# STM32.net
KiCad netlist of a schematic drawn in Altium Designer
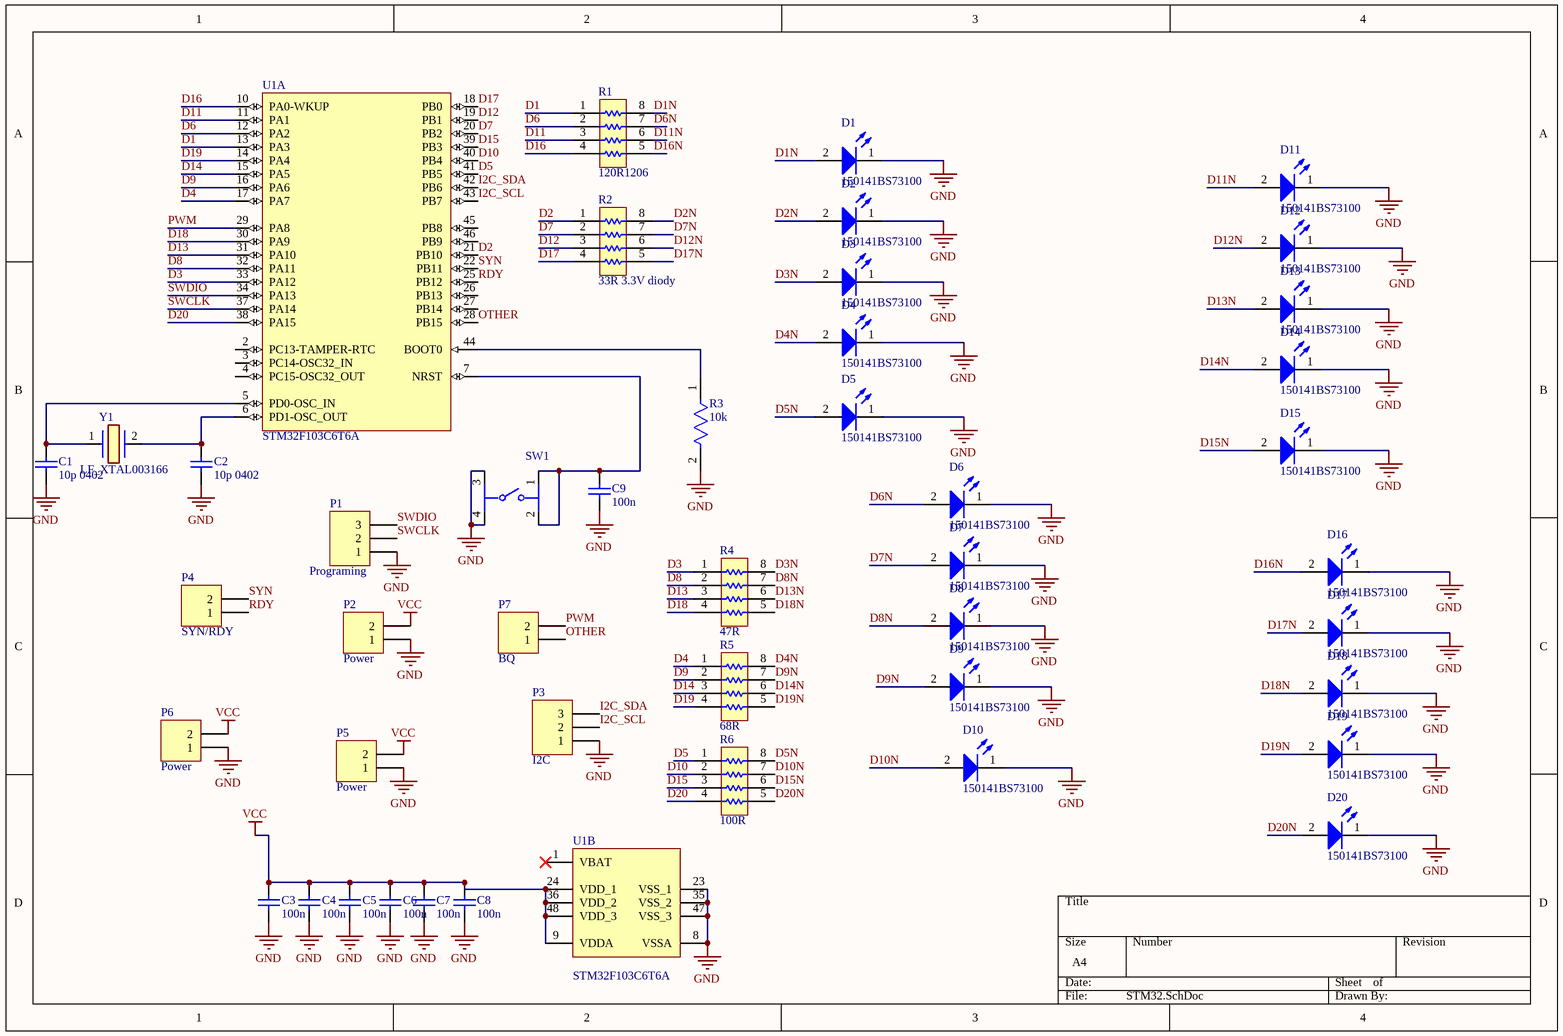
[diagram p0: STM32.SchDoc]

(export (version "E")
  (design (tool "Eeschema 10.0.6"))
  (components
    (comp (ref "C1")
      (value "10p 0402")
      (footprint "CAPC1006X50X20ML10T10")
      (fields
        (field (name "MANUFACTURER") "AVX Interconnect / Elco")
        (field (name "PART NUMBER") "0402YJ100FBSTR")
      )
      (libsource (lib "Altium Content Vault") (part "CAP"))
    )
    (comp (ref "C2")
      (value "10p 0402")
      (footprint "CAPC1006X50X20ML10T10")
      (fields
        (field (name "MANUFACTURER") "AVX Interconnect / Elco")
        (field (name "PART NUMBER") "0402YJ100FBSTR")
      )
      (libsource (lib "Altium Content Vault") (part "CAP"))
    )
    (comp (ref "C3")
      (value "100n")
      (footprint "1608[0603]")
      (description "Capacitor (Semiconductor SIM Model)")
      (fields (field (name "PUBLISHER") "Altium Limited"))
      (libsource (lib "Miscellaneous Devices") (part "Cap Semi"))
    )
    (comp (ref "C4")
      (value "100n")
      (footprint "1608[0603]")
      (description "Capacitor (Semiconductor SIM Model)")
      (fields (field (name "PUBLISHER") "Altium Limited"))
      (libsource (lib "Miscellaneous Devices") (part "Cap Semi"))
    )
    (comp (ref "C5")
      (value "100n")
      (footprint "1608[0603]")
      (description "Capacitor (Semiconductor SIM Model)")
      (fields (field (name "PUBLISHER") "Altium Limited"))
      (libsource (lib "Miscellaneous Devices") (part "Cap Semi"))
    )
    (comp (ref "C6")
      (value "100n")
      (footprint "1608[0603]")
      (description "Capacitor (Semiconductor SIM Model)")
      (fields (field (name "PUBLISHER") "Altium Limited"))
      (libsource (lib "Miscellaneous Devices") (part "Cap Semi"))
    )
    (comp (ref "C7")
      (value "100n")
      (footprint "1608[0603]")
      (description "Capacitor (Semiconductor SIM Model)")
      (fields (field (name "PUBLISHER") "Altium Limited"))
      (libsource (lib "Miscellaneous Devices") (part "Cap Semi"))
    )
    (comp (ref "C8")
      (value "100n")
      (footprint "1608[0603]")
      (description "Capacitor (Semiconductor SIM Model)")
      (fields (field (name "PUBLISHER") "Altium Limited"))
      (libsource (lib "Miscellaneous Devices") (part "Cap Semi"))
    )
    (comp (ref "C9")
      (value "100n")
      (footprint "1608[0603]")
      (description "Capacitor (Semiconductor SIM Model)")
      (fields (field (name "PUBLISHER") "Altium Limited"))
      (libsource (lib "Miscellaneous Devices") (part "Cap Semi"))
    )
    (comp (ref "D1")
      (value "150141BS73100")
      (footprint "WL-SMTW_3528")
      (libsource (lib "Altium Content Vault") (part "LED_Blue_2A-1K"))
    )
    (comp (ref "D2")
      (value "150141BS73100")
      (footprint "WL-SMTW_3528")
      (libsource (lib "Altium Content Vault") (part "LED_Blue_2A-1K"))
    )
    (comp (ref "D3")
      (value "150141BS73100")
      (footprint "WL-SMTW_3528")
      (libsource (lib "Altium Content Vault") (part "LED_Blue_2A-1K"))
    )
    (comp (ref "D4")
      (value "150141BS73100")
      (footprint "WL-SMTW_3528")
      (libsource (lib "Altium Content Vault") (part "LED_Blue_2A-1K"))
    )
    (comp (ref "D5")
      (value "150141BS73100")
      (footprint "WL-SMTW_3528")
      (libsource (lib "Altium Content Vault") (part "LED_Blue_2A-1K"))
    )
    (comp (ref "D6")
      (value "150141BS73100")
      (footprint "WL-SMTW_3528")
      (libsource (lib "Altium Content Vault") (part "LED_Blue_2A-1K"))
    )
    (comp (ref "D7")
      (value "150141BS73100")
      (footprint "WL-SMTW_3528")
      (libsource (lib "Altium Content Vault") (part "LED_Blue_2A-1K"))
    )
    (comp (ref "D8")
      (value "150141BS73100")
      (footprint "WL-SMTW_3528")
      (libsource (lib "Altium Content Vault") (part "LED_Blue_2A-1K"))
    )
    (comp (ref "D9")
      (value "150141BS73100")
      (footprint "WL-SMTW_3528")
      (libsource (lib "Altium Content Vault") (part "LED_Blue_2A-1K"))
    )
    (comp (ref "D10")
      (value "150141BS73100")
      (footprint "WL-SMTW_3528")
      (libsource (lib "Altium Content Vault") (part "LED_Blue_2A-1K"))
    )
    (comp (ref "D11")
      (value "150141BS73100")
      (footprint "WL-SMTW_3528")
      (libsource (lib "Altium Content Vault") (part "LED_Blue_2A-1K"))
    )
    (comp (ref "D12")
      (value "150141BS73100")
      (footprint "WL-SMTW_3528")
      (libsource (lib "Altium Content Vault") (part "LED_Blue_2A-1K"))
    )
    (comp (ref "D13")
      (value "150141BS73100")
      (footprint "WL-SMTW_3528")
      (libsource (lib "Altium Content Vault") (part "LED_Blue_2A-1K"))
    )
    (comp (ref "D14")
      (value "150141BS73100")
      (footprint "WL-SMTW_3528")
      (libsource (lib "Altium Content Vault") (part "LED_Blue_2A-1K"))
    )
    (comp (ref "D15")
      (value "150141BS73100")
      (footprint "WL-SMTW_3528")
      (libsource (lib "Altium Content Vault") (part "LED_Blue_2A-1K"))
    )
    (comp (ref "D16")
      (value "150141BS73100")
      (footprint "WL-SMTW_3528")
      (libsource (lib "Altium Content Vault") (part "LED_Blue_2A-1K"))
    )
    (comp (ref "D17")
      (value "150141BS73100")
      (footprint "WL-SMTW_3528")
      (libsource (lib "Altium Content Vault") (part "LED_Blue_2A-1K"))
    )
    (comp (ref "D18")
      (value "150141BS73100")
      (footprint "WL-SMTW_3528")
      (libsource (lib "Altium Content Vault") (part "LED_Blue_2A-1K"))
    )
    (comp (ref "D19")
      (value "150141BS73100")
      (footprint "WL-SMTW_3528")
      (libsource (lib "Altium Content Vault") (part "LED_Blue_2A-1K"))
    )
    (comp (ref "D20")
      (value "150141BS73100")
      (footprint "WL-SMTW_3528")
      (libsource (lib "Altium Content Vault") (part "LED_Blue_2A-1K"))
    )
    (comp (ref "P1")
      (value "Programing")
      (footprint "HDR1X3")
      (description "Header, 3-Pin")
      (fields (field (name "PUBLISHER") "Altium Limited"))
      (libsource (lib "PreEngProject") (part "Header 3"))
    )
    (comp (ref "P2")
      (value "Power")
      (footprint "HDR1X2")
      (description "Header, 2-Pin")
      (fields (field (name "PUBLISHER") "Altium Limited"))
      (libsource (lib "Miscellaneous Connectors") (part "Header 2"))
    )
    (comp (ref "P3")
      (value "I2C")
      (footprint "HDR1X3")
      (description "Header, 3-Pin")
      (fields (field (name "PUBLISHER") "Altium Limited"))
      (libsource (lib "PreEngProject") (part "Header 3"))
    )
    (comp (ref "P4")
      (value "SYN/RDY")
      (footprint "HDR1X2")
      (description "Header, 2-Pin")
      (fields (field (name "PUBLISHER") "Altium Limited"))
      (libsource (lib "Miscellaneous Connectors") (part "Header 2"))
    )
    (comp (ref "P5")
      (value "Power")
      (footprint "HDR1X2")
      (description "Header, 2-Pin")
      (fields (field (name "PUBLISHER") "Altium Limited"))
      (libsource (lib "Miscellaneous Connectors") (part "Header 2"))
    )
    (comp (ref "P6")
      (value "Power")
      (footprint "HDR1X2")
      (description "Header, 2-Pin")
      (fields (field (name "PUBLISHER") "Altium Limited"))
      (libsource (lib "Miscellaneous Connectors") (part "Header 2"))
    )
    (comp (ref "P7")
      (value "BQ")
      (footprint "HDR1X2")
      (description "Header, 2-Pin")
      (fields (field (name "PUBLISHER") "Altium Limited"))
      (libsource (lib "Miscellaneous Connectors") (part "Header 2"))
    )
    (comp (ref "R1")
      (value "120R1206")
      (footprint "BOUR-CAY16-J4_V")
      (description "Chip Resistor Array, 1 KOhm, +/- 5%, 62.5 mW, -55 to 125 degC, 8-Pin SMD, RoHS, Tape and Reel")
      (fields (field (name "TOLERANCE") "1%"))
      (libsource (lib "Altium Content Vault") (part "RES-P-8"))
    )
    (comp (ref "R2")
      (value "33R 3.3V diody")
      (footprint "BOUR-CAY16-J4_V")
      (description "Chip Resistor Array, 1 KOhm, +/- 5%, 62.5 mW, -55 to 125 degC, 8-Pin SMD, RoHS, Tape and Reel")
      (fields (field (name "TOLERANCE") "1%"))
      (libsource (lib "Altium Content Vault") (part "RES-P-8"))
    )
    (comp (ref "R3")
      (value "10k")
      (footprint "FP-CRCW0603-e3-MFG")
      (description "RES Thick Film, 10kΩ, 1%, 0.1W, 100ppm/°C, 0603")
      (fields (field (name "TOLERANCE") "1%"))
      (libsource (lib "Altium Content Vault") (part "1029c3af85768c4190bb7ad29bc67b5"))
    )
    (comp (ref "R4")
      (value "47R")
      (footprint "BOUR-CAY16-J4_V")
      (description "Chip Resistor Array, 1 KOhm, +/- 5%, 62.5 mW, -55 to 125 degC, 8-Pin SMD, RoHS, Tape and Reel")
      (fields (field (name "TOLERANCE") "1%"))
      (libsource (lib "Altium Content Vault") (part "RES-P-8"))
    )
    (comp (ref "R5")
      (value "68R")
      (footprint "BOUR-CAY16-J4_V")
      (description "Chip Resistor Array, 1 KOhm, +/- 5%, 62.5 mW, -55 to 125 degC, 8-Pin SMD, RoHS, Tape and Reel")
      (fields (field (name "TOLERANCE") "1%"))
      (libsource (lib "Altium Content Vault") (part "RES-P-8"))
    )
    (comp (ref "R6")
      (value "100R")
      (footprint "BOUR-CAY16-J4_V")
      (description "Chip Resistor Array, 1 KOhm, +/- 5%, 62.5 mW, -55 to 125 degC, 8-Pin SMD, RoHS, Tape and Reel")
      (fields (field (name "TOLERANCE") "1%"))
      (libsource (lib "Altium Content Vault") (part "RES-P-8"))
    )
    (comp (ref "SW1")
      (value "PTS645SM43SMTR92LFS")
      (footprint "FP-PTS645SM43SMTR92LFS-MFG")
      (description "SWITCH TACTILE SPST-NO 0.05A 12V")
      (libsource (lib "Altium Content Vault") (part "1adf0dd01260c80cf25a44bfd6b99ba"))
    )
    (comp (ref "U1")
      (value "STM32F103C6T6A")
      (footprint "STM-LQFP48_L")
      (libsource (lib "Altium Content Vault") (part "MC-ARM-STM32F103X4_6-SQ48"))
    )
    (comp (ref "Y1")
      (value "LF_XTAL003166")
      (footprint "SamacSys:LFXTAL003166")
      (description "Crystal or Oscillator")
      (fields (field (name "MANUFACTURER_PART_NUMBER") "LF XTAL003166"))
      (libsource (lib "*") (part "LF_XTAL003166"))
    )
  )
  (nets
    (net (code "1") (name "/D1") (class "Default")
      (node (ref "R1") (pin "1") (pinfunction "1_1") (pintype "passive"))
      (node (ref "U1") (pin "13") (pinfunction "PA3_13") (pintype "bidirectional"))
    )
    (net (code "2") (name "/D1N") (class "Default")
      (node (ref "D1") (pin "2") (pinfunction "A_2") (pintype "passive"))
      (node (ref "R1") (pin "8") (pinfunction "8_8") (pintype "passive"))
    )
    (net (code "3") (name "/D2") (class "Default")
      (node (ref "R2") (pin "1") (pinfunction "1_1") (pintype "passive"))
      (node (ref "U1") (pin "21") (pinfunction "PB10_21") (pintype "bidirectional"))
    )
    (net (code "4") (name "/D2N") (class "Default")
      (node (ref "D2") (pin "2") (pinfunction "A_2") (pintype "passive"))
      (node (ref "R2") (pin "8") (pinfunction "8_8") (pintype "passive"))
    )
    (net (code "5") (name "/D3") (class "Default")
      (node (ref "R4") (pin "1") (pinfunction "1_1") (pintype "passive"))
      (node (ref "U1") (pin "33") (pinfunction "PA12_33") (pintype "bidirectional"))
    )
    (net (code "6") (name "/D3N") (class "Default")
      (node (ref "D3") (pin "2") (pinfunction "A_2") (pintype "passive"))
      (node (ref "R4") (pin "8") (pinfunction "8_8") (pintype "passive"))
    )
    (net (code "7") (name "/D4") (class "Default")
      (node (ref "R5") (pin "1") (pinfunction "1_1") (pintype "passive"))
      (node (ref "U1") (pin "17") (pinfunction "PA7_17") (pintype "bidirectional"))
    )
    (net (code "8") (name "/D4N") (class "Default")
      (node (ref "D4") (pin "2") (pinfunction "A_2") (pintype "passive"))
      (node (ref "R5") (pin "8") (pinfunction "8_8") (pintype "passive"))
    )
    (net (code "9") (name "/D5") (class "Default")
      (node (ref "R6") (pin "1") (pinfunction "1_1") (pintype "passive"))
      (node (ref "U1") (pin "41") (pinfunction "PB5_41") (pintype "bidirectional"))
    )
    (net (code "10") (name "/D5N") (class "Default")
      (node (ref "D5") (pin "2") (pinfunction "A_2") (pintype "passive"))
      (node (ref "R6") (pin "8") (pinfunction "8_8") (pintype "passive"))
    )
    (net (code "11") (name "/D6") (class "Default")
      (node (ref "R1") (pin "2") (pinfunction "2_2") (pintype "passive"))
      (node (ref "U1") (pin "12") (pinfunction "PA2_12") (pintype "bidirectional"))
    )
    (net (code "12") (name "/D6N") (class "Default")
      (node (ref "D6") (pin "2") (pinfunction "A_2") (pintype "passive"))
      (node (ref "R1") (pin "7") (pinfunction "7_7") (pintype "passive"))
    )
    (net (code "13") (name "/D7") (class "Default")
      (node (ref "R2") (pin "2") (pinfunction "2_2") (pintype "passive"))
      (node (ref "U1") (pin "20") (pinfunction "PB2_20") (pintype "bidirectional"))
    )
    (net (code "14") (name "/D7N") (class "Default")
      (node (ref "D7") (pin "2") (pinfunction "A_2") (pintype "passive"))
      (node (ref "R2") (pin "7") (pinfunction "7_7") (pintype "passive"))
    )
    (net (code "15") (name "/D8") (class "Default")
      (node (ref "R4") (pin "2") (pinfunction "2_2") (pintype "passive"))
      (node (ref "U1") (pin "32") (pinfunction "PA11_32") (pintype "bidirectional"))
    )
    (net (code "16") (name "/D8N") (class "Default")
      (node (ref "D8") (pin "2") (pinfunction "A_2") (pintype "passive"))
      (node (ref "R4") (pin "7") (pinfunction "7_7") (pintype "passive"))
    )
    (net (code "17") (name "/D9") (class "Default")
      (node (ref "R5") (pin "2") (pinfunction "2_2") (pintype "passive"))
      (node (ref "U1") (pin "16") (pinfunction "PA6_16") (pintype "bidirectional"))
    )
    (net (code "18") (name "/D9N") (class "Default")
      (node (ref "D9") (pin "2") (pinfunction "A_2") (pintype "passive"))
      (node (ref "R5") (pin "7") (pinfunction "7_7") (pintype "passive"))
    )
    (net (code "19") (name "/D10") (class "Default")
      (node (ref "R6") (pin "2") (pinfunction "2_2") (pintype "passive"))
      (node (ref "U1") (pin "40") (pinfunction "PB4_40") (pintype "bidirectional"))
    )
    (net (code "20") (name "/D10N") (class "Default")
      (node (ref "D10") (pin "2") (pinfunction "A_2") (pintype "passive"))
      (node (ref "R6") (pin "7") (pinfunction "7_7") (pintype "passive"))
    )
    (net (code "21") (name "/D11") (class "Default")
      (node (ref "R1") (pin "3") (pinfunction "3_3") (pintype "passive"))
      (node (ref "U1") (pin "11") (pinfunction "PA1_11") (pintype "bidirectional"))
    )
    (net (code "22") (name "/D11N") (class "Default")
      (node (ref "D11") (pin "2") (pinfunction "A_2") (pintype "passive"))
      (node (ref "R1") (pin "6") (pinfunction "6_6") (pintype "passive"))
    )
    (net (code "23") (name "/D12") (class "Default")
      (node (ref "R2") (pin "3") (pinfunction "3_3") (pintype "passive"))
      (node (ref "U1") (pin "19") (pinfunction "PB1_19") (pintype "bidirectional"))
    )
    (net (code "24") (name "/D12N") (class "Default")
      (node (ref "D12") (pin "2") (pinfunction "A_2") (pintype "passive"))
      (node (ref "R2") (pin "6") (pinfunction "6_6") (pintype "passive"))
    )
    (net (code "25") (name "/D13") (class "Default")
      (node (ref "R4") (pin "3") (pinfunction "3_3") (pintype "passive"))
      (node (ref "U1") (pin "31") (pinfunction "PA10_31") (pintype "bidirectional"))
    )
    (net (code "26") (name "/D13N") (class "Default")
      (node (ref "D13") (pin "2") (pinfunction "A_2") (pintype "passive"))
      (node (ref "R4") (pin "6") (pinfunction "6_6") (pintype "passive"))
    )
    (net (code "27") (name "/D14") (class "Default")
      (node (ref "R5") (pin "3") (pinfunction "3_3") (pintype "passive"))
      (node (ref "U1") (pin "15") (pinfunction "PA5_15") (pintype "bidirectional"))
    )
    (net (code "28") (name "/D14N") (class "Default")
      (node (ref "D14") (pin "2") (pinfunction "A_2") (pintype "passive"))
      (node (ref "R5") (pin "6") (pinfunction "6_6") (pintype "passive"))
    )
    (net (code "29") (name "/D15") (class "Default")
      (node (ref "R6") (pin "3") (pinfunction "3_3") (pintype "passive"))
      (node (ref "U1") (pin "39") (pinfunction "PB3_39") (pintype "bidirectional"))
    )
    (net (code "30") (name "/D15N") (class "Default")
      (node (ref "D15") (pin "2") (pinfunction "A_2") (pintype "passive"))
      (node (ref "R6") (pin "6") (pinfunction "6_6") (pintype "passive"))
    )
    (net (code "31") (name "/D16") (class "Default")
      (node (ref "R1") (pin "4") (pinfunction "4_4") (pintype "passive"))
      (node (ref "U1") (pin "10") (pinfunction "PA0-WKUP_10") (pintype "bidirectional"))
    )
    (net (code "32") (name "/D16N") (class "Default")
      (node (ref "D16") (pin "2") (pinfunction "A_2") (pintype "passive"))
      (node (ref "R1") (pin "5") (pinfunction "5_5") (pintype "passive"))
    )
    (net (code "33") (name "/D17") (class "Default")
      (node (ref "R2") (pin "4") (pinfunction "4_4") (pintype "passive"))
      (node (ref "U1") (pin "18") (pinfunction "PB0_18") (pintype "bidirectional"))
    )
    (net (code "34") (name "/D17N") (class "Default")
      (node (ref "D17") (pin "2") (pinfunction "A_2") (pintype "passive"))
      (node (ref "R2") (pin "5") (pinfunction "5_5") (pintype "passive"))
    )
    (net (code "35") (name "/D18") (class "Default")
      (node (ref "R4") (pin "4") (pinfunction "4_4") (pintype "passive"))
      (node (ref "U1") (pin "30") (pinfunction "PA9_30") (pintype "bidirectional"))
    )
    (net (code "36") (name "/D18N") (class "Default")
      (node (ref "D18") (pin "2") (pinfunction "A_2") (pintype "passive"))
      (node (ref "R4") (pin "5") (pinfunction "5_5") (pintype "passive"))
    )
    (net (code "37") (name "/D19") (class "Default")
      (node (ref "R5") (pin "4") (pinfunction "4_4") (pintype "passive"))
      (node (ref "U1") (pin "14") (pinfunction "PA4_14") (pintype "bidirectional"))
    )
    (net (code "38") (name "/D19N") (class "Default")
      (node (ref "D19") (pin "2") (pinfunction "A_2") (pintype "passive"))
      (node (ref "R5") (pin "5") (pinfunction "5_5") (pintype "passive"))
    )
    (net (code "39") (name "/D20") (class "Default")
      (node (ref "R6") (pin "4") (pinfunction "4_4") (pintype "passive"))
      (node (ref "U1") (pin "38") (pinfunction "PA15_38") (pintype "bidirectional"))
    )
    (net (code "40") (name "/D20N") (class "Default")
      (node (ref "D20") (pin "2") (pinfunction "A_2") (pintype "passive"))
      (node (ref "R6") (pin "5") (pinfunction "5_5") (pintype "passive"))
    )
    (net (code "41") (name "/I2C_SCL") (class "Default")
      (node (ref "P3") (pin "2") (pinfunction "2_2") (pintype "passive"))
      (node (ref "U1") (pin "43") (pinfunction "PB7_43") (pintype "bidirectional"))
    )
    (net (code "42") (name "/I2C_SDA") (class "Default")
      (node (ref "P3") (pin "3") (pinfunction "3_3") (pintype "passive"))
      (node (ref "U1") (pin "42") (pinfunction "PB6_42") (pintype "bidirectional"))
    )
    (net (code "43") (name "/OTHER") (class "Default")
      (node (ref "P7") (pin "1") (pinfunction "1_1") (pintype "passive"))
      (node (ref "U1") (pin "28") (pinfunction "PB15_28") (pintype "bidirectional"))
    )
    (net (code "44") (name "/PWM") (class "Default")
      (node (ref "P7") (pin "2") (pinfunction "2_2") (pintype "passive"))
      (node (ref "U1") (pin "29") (pinfunction "PA8_29") (pintype "bidirectional"))
    )
    (net (code "45") (name "/RDY") (class "Default")
      (node (ref "P4") (pin "1") (pinfunction "1_1") (pintype "passive"))
      (node (ref "U1") (pin "25") (pinfunction "PB12_25") (pintype "bidirectional"))
    )
    (net (code "46") (name "/SWCLK") (class "Default")
      (node (ref "P1") (pin "2") (pinfunction "2_2") (pintype "passive"))
      (node (ref "U1") (pin "37") (pinfunction "PA14_37") (pintype "bidirectional"))
    )
    (net (code "47") (name "/SWDIO") (class "Default")
      (node (ref "P1") (pin "3") (pinfunction "3_3") (pintype "passive"))
      (node (ref "U1") (pin "34") (pinfunction "PA13_34") (pintype "bidirectional"))
    )
    (net (code "48") (name "/SYN") (class "Default")
      (node (ref "P4") (pin "2") (pinfunction "2_2") (pintype "passive"))
      (node (ref "U1") (pin "22") (pinfunction "PB11_22") (pintype "bidirectional"))
    )
    (net (code "49") (name "GND") (class "Default")
      (node (ref "C1") (pin "1") (pinfunction "1_1") (pintype "passive"))
      (node (ref "C2") (pin "1") (pinfunction "1_1") (pintype "passive"))
      (node (ref "C3") (pin "1") (pinfunction "1_1") (pintype "passive"))
      (node (ref "C4") (pin "1") (pinfunction "1_1") (pintype "passive"))
      (node (ref "C5") (pin "1") (pinfunction "1_1") (pintype "passive"))
      (node (ref "C6") (pin "1") (pinfunction "1_1") (pintype "passive"))
      (node (ref "C7") (pin "1") (pinfunction "1_1") (pintype "passive"))
      (node (ref "C8") (pin "1") (pinfunction "1_1") (pintype "passive"))
      (node (ref "C9") (pin "1") (pinfunction "1_1") (pintype "passive"))
      (node (ref "D1") (pin "1") (pinfunction "K_1") (pintype "passive"))
      (node (ref "D10") (pin "1") (pinfunction "K_1") (pintype "passive"))
      (node (ref "D11") (pin "1") (pinfunction "K_1") (pintype "passive"))
      (node (ref "D12") (pin "1") (pinfunction "K_1") (pintype "passive"))
      (node (ref "D13") (pin "1") (pinfunction "K_1") (pintype "passive"))
      (node (ref "D14") (pin "1") (pinfunction "K_1") (pintype "passive"))
      (node (ref "D15") (pin "1") (pinfunction "K_1") (pintype "passive"))
      (node (ref "D16") (pin "1") (pinfunction "K_1") (pintype "passive"))
      (node (ref "D17") (pin "1") (pinfunction "K_1") (pintype "passive"))
      (node (ref "D18") (pin "1") (pinfunction "K_1") (pintype "passive"))
      (node (ref "D19") (pin "1") (pinfunction "K_1") (pintype "passive"))
      (node (ref "D2") (pin "1") (pinfunction "K_1") (pintype "passive"))
      (node (ref "D20") (pin "1") (pinfunction "K_1") (pintype "passive"))
      (node (ref "D3") (pin "1") (pinfunction "K_1") (pintype "passive"))
      (node (ref "D4") (pin "1") (pinfunction "K_1") (pintype "passive"))
      (node (ref "D5") (pin "1") (pinfunction "K_1") (pintype "passive"))
      (node (ref "D6") (pin "1") (pinfunction "K_1") (pintype "passive"))
      (node (ref "D7") (pin "1") (pinfunction "K_1") (pintype "passive"))
      (node (ref "D8") (pin "1") (pinfunction "K_1") (pintype "passive"))
      (node (ref "D9") (pin "1") (pinfunction "K_1") (pintype "passive"))
      (node (ref "P1") (pin "1") (pinfunction "1_1") (pintype "passive"))
      (node (ref "P2") (pin "1") (pinfunction "1_1") (pintype "passive"))
      (node (ref "P3") (pin "1") (pinfunction "1_1") (pintype "passive"))
      (node (ref "P5") (pin "1") (pinfunction "1_1") (pintype "passive"))
      (node (ref "P6") (pin "1") (pinfunction "1_1") (pintype "passive"))
      (node (ref "R3") (pin "2") (pinfunction "2_2") (pintype "passive"))
      (node (ref "SW1") (pin "3") (pinfunction "3_3") (pintype "passive"))
      (node (ref "SW1") (pin "4") (pinfunction "4_4") (pintype "passive"))
      (node (ref "U1") (pin "23") (pinfunction "VSS_1_23") (pintype "power_in"))
      (node (ref "U1") (pin "35") (pinfunction "VSS_2_35") (pintype "power_in"))
      (node (ref "U1") (pin "47") (pinfunction "VSS_3_47") (pintype "power_in"))
      (node (ref "U1") (pin "8") (pinfunction "VSSA_8") (pintype "power_in"))
    )
    (net (code "50") (name "Net-(U1A-BOOT0)") (class "Default")
      (node (ref "R3") (pin "1") (pinfunction "1_1") (pintype "passive"))
      (node (ref "U1") (pin "44") (pinfunction "BOOT0_44") (pintype "input"))
    )
    (net (code "51") (name "Net-(U1A-NRST)") (class "Default")
      (node (ref "C9") (pin "2") (pinfunction "2_2") (pintype "passive"))
      (node (ref "SW1") (pin "1") (pinfunction "1_1") (pintype "passive"))
      (node (ref "SW1") (pin "2") (pinfunction "2_2") (pintype "passive"))
      (node (ref "U1") (pin "7") (pinfunction "NRST_7") (pintype "bidirectional"))
    )
    (net (code "52") (name "Net-(U1A-PD0-OSC_IN)") (class "Default")
      (node (ref "C1") (pin "2") (pinfunction "2_2") (pintype "passive"))
      (node (ref "U1") (pin "5") (pinfunction "PD0-OSC_IN_5") (pintype "bidirectional"))
      (node (ref "Y1") (pin "1") (pinfunction "1_1") (pintype "passive"))
    )
    (net (code "53") (name "Net-(U1A-PD1-OSC_OUT)") (class "Default")
      (node (ref "C2") (pin "2") (pinfunction "2_2") (pintype "passive"))
      (node (ref "U1") (pin "6") (pinfunction "PD1-OSC_OUT_6") (pintype "bidirectional"))
      (node (ref "Y1") (pin "2") (pinfunction "2_2") (pintype "passive"))
    )
    (net (code "54") (name "VCC") (class "Default")
      (node (ref "C3") (pin "2") (pinfunction "2_2") (pintype "passive"))
      (node (ref "C4") (pin "2") (pinfunction "2_2") (pintype "passive"))
      (node (ref "C5") (pin "2") (pinfunction "2_2") (pintype "passive"))
      (node (ref "C6") (pin "2") (pinfunction "2_2") (pintype "passive"))
      (node (ref "C7") (pin "2") (pinfunction "2_2") (pintype "passive"))
      (node (ref "C8") (pin "2") (pinfunction "2_2") (pintype "passive"))
      (node (ref "P2") (pin "2") (pinfunction "2_2") (pintype "passive"))
      (node (ref "P5") (pin "2") (pinfunction "2_2") (pintype "passive"))
      (node (ref "P6") (pin "2") (pinfunction "2_2") (pintype "passive"))
      (node (ref "U1") (pin "24") (pinfunction "VDD_1_24") (pintype "power_in"))
      (node (ref "U1") (pin "36") (pinfunction "VDD_2_36") (pintype "power_in"))
      (node (ref "U1") (pin "48") (pinfunction "VDD_3_48") (pintype "power_in"))
      (node (ref "U1") (pin "9") (pinfunction "VDDA_9") (pintype "power_in"))
    )
    (net (code "55") (name "unconnected-(U1A-PB8-Pad45)") (class "Default")
      (node (ref "U1") (pin "45") (pinfunction "PB8_45") (pintype "bidirectional"))
    )
    (net (code "56") (name "unconnected-(U1A-PB9-Pad46)") (class "Default")
      (node (ref "U1") (pin "46") (pinfunction "PB9_46") (pintype "bidirectional"))
    )
    (net (code "57") (name "unconnected-(U1A-PB13-Pad26)") (class "Default")
      (node (ref "U1") (pin "26") (pinfunction "PB13_26") (pintype "bidirectional"))
    )
    (net (code "58") (name "unconnected-(U1A-PB14-Pad27)") (class "Default")
      (node (ref "U1") (pin "27") (pinfunction "PB14_27") (pintype "bidirectional"))
    )
    (net (code "59") (name "unconnected-(U1A-PC13-TAMPER-RTC-Pad2)") (class "Default")
      (node (ref "U1") (pin "2") (pinfunction "PC13-TAMPER-RTC_2") (pintype "bidirectional"))
    )
    (net (code "60") (name "unconnected-(U1A-PC14-OSC32_IN-Pad3)") (class "Default")
      (node (ref "U1") (pin "3") (pinfunction "PC14-OSC32_IN_3") (pintype "bidirectional"))
    )
    (net (code "61") (name "unconnected-(U1A-PC15-OSC32_OUT-Pad4)") (class "Default")
      (node (ref "U1") (pin "4") (pinfunction "PC15-OSC32_OUT_4") (pintype "bidirectional"))
    )
    (net (code "62") (name "unconnected-(U1B-VBAT-Pad1)") (class "Default")
      (node (ref "U1") (pin "1") (pinfunction "VBAT_1") (pintype "power_in+no_connect"))
    )
  )
)
